# Low_noise_PSU.net
KiCad netlist of a schematic drawn in Altium Designer
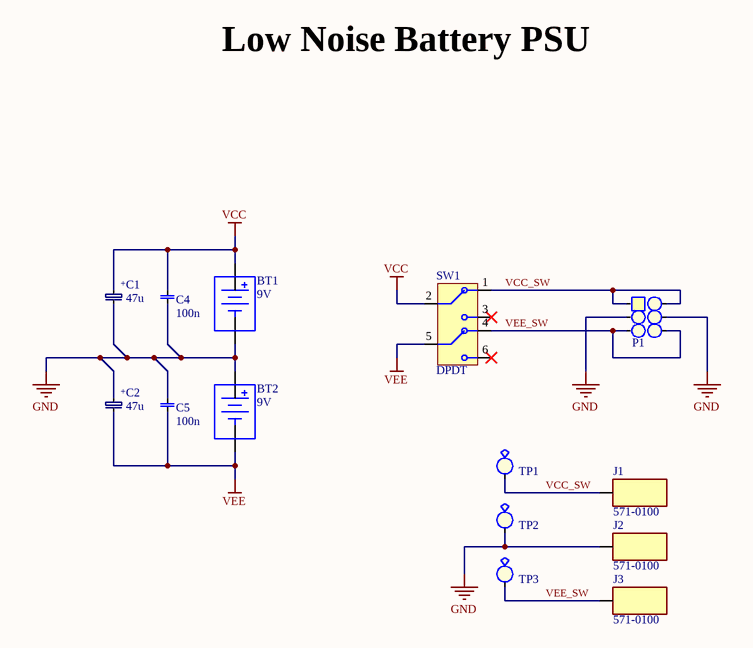
[diagram p0: Low noise PSU.SchDoc]

(export (version "E")
  (design (tool "Eeschema 10.0.6"))
  (components
    (comp (ref "BT1")
      (value "9V")
      (footprint "Battery_Holder_9V")
      (description "Electrokit art nr: 41003388")
      (libsource (lib "jclib") (part "Battery Holder 9V"))
    )
    (comp (ref "BT2")
      (value "9V")
      (footprint "Battery_Holder_9V")
      (description "Electrokit art nr: 41003388")
      (libsource (lib "jclib") (part "Battery Holder 9V"))
    )
    (comp (ref "C1")
      (value "47u")
      (footprint "Capacitor TH 6.3x12.5mm P2.5mm")
      (description "Capacitor TH Polarized")
      (fields (field (name "Comment") "Capacitor, TH Polarized"))
      (libsource (lib "jclib") (part "Capacitor, TH Polarized"))
    )
    (comp (ref "C2")
      (value "47u")
      (footprint "Capacitor TH 6.3x12.5mm P2.5mm")
      (description "Capacitor TH Polarized")
      (fields (field (name "Comment") "Capacitor, TH Polarized"))
      (libsource (lib "jclib") (part "Capacitor, TH Polarized"))
    )
    (comp (ref "C4")
      (value "100n")
      (footprint "0805, cap")
      (fields (field (name "Comment") "0805, capacitor"))
      (libsource (lib "jclib") (part "0805, capacitor"))
    )
    (comp (ref "C5")
      (value "100n")
      (footprint "0805, cap")
      (fields (field (name "Comment") "0805, capacitor"))
      (libsource (lib "jclib") (part "0805, capacitor"))
    )
    (comp (ref "J1")
      (value "571-0100")
      (footprint "Banana Conn VCC")
      (description "Banana Connector 571-0100")
      (fields (field (name "MOUSER PART NUMBER") "164-6218"))
      (libsource (lib "jclib") (part "Banana conn"))
    )
    (comp (ref "J2")
      (value "571-0100")
      (footprint "Banana Conn VCC")
      (description "Banana Connector 571-0100")
      (fields (field (name "MOUSER PART NUMBER") "164-6218"))
      (libsource (lib "jclib") (part "Banana conn"))
    )
    (comp (ref "J3")
      (value "571-0100")
      (footprint "Banana Conn VCC")
      (description "Banana Connector 571-0100")
      (fields (field (name "MOUSER PART NUMBER") "164-6218"))
      (libsource (lib "jclib") (part "Banana conn"))
    )
    (comp (ref "P1")
      (value "2x3 Pin Header")
      (footprint "2x3 PH")
      (libsource (lib "jclib") (part "2x3 Pin Header"))
    )
    (comp (ref "SW1")
      (value "DPDT")
      (footprint "SW_DPDT_MTS-202-A2")
      (description "Toggle switch DPDT")
      (libsource (lib "jclib") (part "Switch DPDT"))
    )
    (comp (ref "TP1")
      (value "Test Point")
      (footprint "TESTPOINT_SMD")
      (libsource (lib "jclib") (part "Test Point"))
    )
    (comp (ref "TP2")
      (value "Test Point")
      (footprint "TESTPOINT_SMD")
      (libsource (lib "jclib") (part "Test Point"))
    )
    (comp (ref "TP3")
      (value "Test Point")
      (footprint "TESTPOINT_SMD")
      (libsource (lib "jclib") (part "Test Point"))
    )
  )
  (nets
    (net (code "1") (name "/VCC_SW") (class "Default")
      (node (ref "J1") (pin "1") (pinfunction "1_1") (pintype "passive"))
      (node (ref "P1") (pin "1") (pinfunction "1_1") (pintype "passive"))
      (node (ref "P1") (pin "6") (pinfunction "6_6") (pintype "passive"))
      (node (ref "SW1") (pin "1") (pinfunction "1_1") (pintype "passive"))
      (node (ref "TP1") (pin "0") (pinfunction "0_0") (pintype "passive"))
    )
    (net (code "2") (name "/VEE_SW") (class "Default")
      (node (ref "J3") (pin "1") (pinfunction "1_1") (pintype "passive"))
      (node (ref "P1") (pin "3") (pinfunction "3_3") (pintype "passive"))
      (node (ref "P1") (pin "4") (pinfunction "4_4") (pintype "passive"))
      (node (ref "SW1") (pin "4") (pinfunction "4_4") (pintype "passive"))
      (node (ref "TP3") (pin "0") (pinfunction "0_0") (pintype "passive"))
    )
    (net (code "3") (name "GND") (class "Default")
      (node (ref "BT1") (pin "N") (pinfunction "NEG_N") (pintype "passive"))
      (node (ref "BT2") (pin "P") (pinfunction "POS_P") (pintype "passive"))
      (node (ref "C1") (pin "1") (pinfunction "1_1") (pintype "passive"))
      (node (ref "C2") (pin "2") (pinfunction "2_2") (pintype "passive"))
      (node (ref "C4") (pin "2") (pinfunction "2_2") (pintype "passive"))
      (node (ref "C5") (pin "1") (pinfunction "1_1") (pintype "passive"))
      (node (ref "J2") (pin "1") (pinfunction "1_1") (pintype "passive"))
      (node (ref "P1") (pin "2") (pinfunction "2_2") (pintype "passive"))
      (node (ref "P1") (pin "5") (pinfunction "5_5") (pintype "passive"))
      (node (ref "TP2") (pin "0") (pinfunction "0_0") (pintype "passive"))
    )
    (net (code "4") (name "VCC") (class "Default")
      (node (ref "BT1") (pin "P") (pinfunction "POS_P") (pintype "passive"))
      (node (ref "C1") (pin "2") (pinfunction "2_2") (pintype "passive"))
      (node (ref "C4") (pin "1") (pinfunction "1_1") (pintype "passive"))
      (node (ref "SW1") (pin "2") (pinfunction "2_2") (pintype "passive"))
    )
    (net (code "5") (name "VEE") (class "Default")
      (node (ref "BT2") (pin "N") (pinfunction "NEG_N") (pintype "passive"))
      (node (ref "C2") (pin "1") (pinfunction "1_1") (pintype "passive"))
      (node (ref "C5") (pin "2") (pinfunction "2_2") (pintype "passive"))
      (node (ref "SW1") (pin "5") (pinfunction "5_5") (pintype "passive"))
    )
    (net (code "6") (name "unconnected-(SW1-Pad3)") (class "Default")
      (node (ref "SW1") (pin "3") (pinfunction "3_3") (pintype "passive+no_connect"))
    )
    (net (code "7") (name "unconnected-(SW1-Pad6)") (class "Default")
      (node (ref "SW1") (pin "6") (pinfunction "6_6") (pintype "passive+no_connect"))
    )
  )
)
